# schematic.net
KiCad netlist of a schematic drawn in Altium Designer
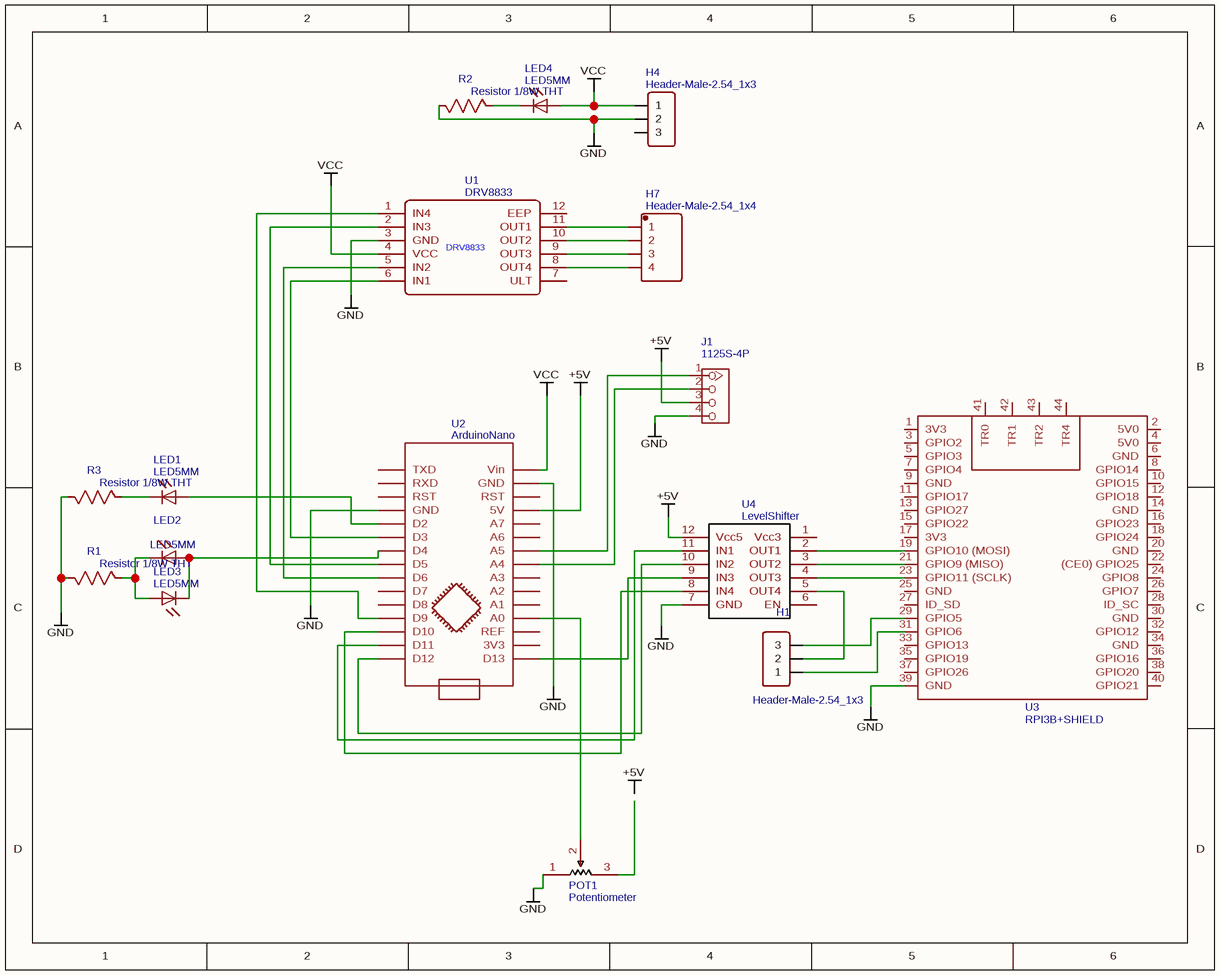
[diagram p0: schematic.schdoc]

(export (version "E")
  (design (tool "Eeschema 10.0.6"))
  (components
    (comp (ref "H1")
      (value "Header-Male-2.54_1x3")
      (fields
        (field (name "BOM_MANUFACTURER PART") "Header2.54mm 1*3P")
        (field (name "BOM_SUPPLIER PART") "C49257")
      )
      (libsource (lib "altium-import") (part "root_2_Header-Male-2.54_1x3_"))
    )
    (comp (ref "H4")
      (value "Header-Male-2.54_1x3")
      (fields
        (field (name "BOM_MANUFACTURER PART") "Header2.54mm 1*3P")
        (field (name "BOM_SUPPLIER PART") "C49257")
      )
      (libsource (lib "altium-import") (part "root_0_Header-Male-2.54_1x3_"))
    )
    (comp (ref "H7")
      (value "Header-Male-2.54_1x4")
      (fields
        (field (name "BOM_MANUFACTURER PART") "210S-1*4P L=11.6MMGold-plated black")
        (field (name "BOM_SUPPLIER PART") "C124378")
        (field (name "CONTRIBUTOR") "LCSC")
      )
      (libsource (lib "altium-import") (part "root_0_Header-Male-2.54_1x4_"))
    )
    (comp (ref "J1")
      (value "1125S-4P")
      (description "DIP Grove")
      (libsource (lib "altium-import") (part "root_0_1125S-4P_"))
    )
    (comp (ref "LED1")
      (value "LED5MM")
      (description "LEDs")
      (fields (field (name "CONTRIBUTOR") "Pinoccio"))
      (libsource (lib "altium-import") (part "root_3_LED5MM_"))
    )
    (comp (ref "LED2")
      (value "LED5MM")
      (description "LEDs")
      (fields (field (name "CONTRIBUTOR") "Pinoccio"))
      (libsource (lib "altium-import") (part "root_3_LED5MM_"))
    )
    (comp (ref "LED3")
      (value "LED5MM")
      (description "LEDs")
      (fields (field (name "CONTRIBUTOR") "Pinoccio"))
      (libsource (lib "altium-import") (part "root_1_LED5MM_"))
    )
    (comp (ref "LED4")
      (value "LED5MM")
      (description "LEDs")
      (fields (field (name "CONTRIBUTOR") "Pinoccio"))
      (libsource (lib "altium-import") (part "root_3_LED5MM_"))
    )
    (comp (ref "POT1")
      (value "Potentiometer")
      (fields
        (field (name "BOM_MANUFACTURER PART") "potentiometer")
        (field (name "CONTRIBUTOR") "Tommaso Mariotti")
      )
      (libsource (lib "altium-import") (part "root_0_Potentiometer_"))
    )
    (comp (ref "R1")
      (value "Resistor 1/8W THT")
      (fields (field (name "BOM_MANUFACTURER PART") "Generic") (field (name "CONTRIBUTOR") "tyvogelpohl"))
      (libsource (lib "altium-import") (part "root_2_Resistor 1/8W THT_"))
    )
    (comp (ref "R2")
      (value "Resistor 1/8W THT")
      (fields (field (name "BOM_MANUFACTURER PART") "Generic") (field (name "CONTRIBUTOR") "tyvogelpohl"))
      (libsource (lib "altium-import") (part "root_2_Resistor 1/8W THT_"))
    )
    (comp (ref "R3")
      (value "Resistor 1/8W THT")
      (fields (field (name "BOM_MANUFACTURER PART") "Generic") (field (name "CONTRIBUTOR") "tyvogelpohl"))
      (libsource (lib "altium-import") (part "root_2_Resistor 1/8W THT_"))
    )
    (comp (ref "U1") (value "DRV8833") (libsource (lib "altium-import") (part "root_0_DRV8833_")))
    (comp (ref "U2")
      (value "ArduinoNano")
      (fields (field (name "CONTRIBUTOR") "vincint810923"))
      (libsource (lib "altium-import") (part "root_0_ArduinoNano_"))
    )
    (comp (ref "U3")
      (value "RPI3B+SHIELD")
      (fields (field (name "BOM_MANUFACTURER PART") "RaspberryPi 3") (field (name "CONTRIBUTOR") "gdevries"))
      (libsource (lib "altium-import") (part "root_0_RPI3B+SHIELD_"))
    )
    (comp (ref "U4")
      (value "LevelShifter")
      (fields (field (name "CONTRIBUTOR") "max.helmrich"))
      (libsource (lib "altium-import") (part "root_0_LevelShifter_"))
    )
  )
  (nets
    (net (code "1") (name "+5V") (class "Default")
      (node (ref "J1") (pin "3") (pinfunction "3_3") (pintype "passive"))
      (node (ref "U2") (pin "27") (pinfunction "5V_27") (pintype "passive"))
      (node (ref "U4") (pin "12") (pinfunction "Vcc5_12") (pintype "passive"))
    )
    (net (code "2") (name "GND") (class "Default")
      (node (ref "H4") (pin "2") (pinfunction "2_2") (pintype "passive"))
      (node (ref "J1") (pin "4") (pinfunction "4_4") (pintype "passive"))
      (node (ref "POT1") (pin "1") (pinfunction "1_1") (pintype "passive"))
      (node (ref "R1") (pin "2") (pinfunction "2_2") (pintype "passive"))
      (node (ref "R2") (pin "2") (pinfunction "2_2") (pintype "passive"))
      (node (ref "R3") (pin "2") (pinfunction "2_2") (pintype "passive"))
      (node (ref "U1") (pin "3") (pinfunction "GND_3") (pintype "passive"))
      (node (ref "U2") (pin "29") (pinfunction "GND_29") (pintype "passive"))
      (node (ref "U2") (pin "4") (pinfunction "GND_4") (pintype "passive"))
      (node (ref "U3") (pin "39") (pinfunction "GND_39") (pintype "passive"))
      (node (ref "U4") (pin "7") (pinfunction "GND_7") (pintype "passive"))
    )
    (net (code "3") (name "Net-(LED1-C)") (class "Default")
      (node (ref "LED1") (pin "K") (pinfunction "C_K") (pintype "passive"))
      (node (ref "R3") (pin "1") (pinfunction "1_1") (pintype "passive"))
    )
    (net (code "4") (name "Net-(LED2-C)") (class "Default")
      (node (ref "LED2") (pin "K") (pinfunction "C_K") (pintype "passive"))
      (node (ref "LED3") (pin "A") (pinfunction "A_A") (pintype "passive"))
      (node (ref "R1") (pin "1") (pinfunction "1_1") (pintype "passive"))
    )
    (net (code "5") (name "Net-(LED3-C)") (class "Default")
      (node (ref "LED2") (pin "A") (pinfunction "A_A") (pintype "passive"))
      (node (ref "LED3") (pin "K") (pinfunction "C_K") (pintype "passive"))
      (node (ref "U2") (pin "7") (pinfunction "D4_7") (pintype "passive"))
    )
    (net (code "6") (name "Net-(LED4-C)") (class "Default")
      (node (ref "LED4") (pin "K") (pinfunction "C_K") (pintype "passive"))
      (node (ref "R2") (pin "1") (pinfunction "1_1") (pintype "passive"))
    )
    (net (code "7") (name "Net-(U1-IN1)") (class "Default")
      (node (ref "U1") (pin "6") (pinfunction "IN1_6") (pintype "passive"))
      (node (ref "U2") (pin "6") (pinfunction "D3_6") (pintype "passive"))
    )
    (net (code "8") (name "Net-(U1-IN2)") (class "Default")
      (node (ref "U1") (pin "5") (pinfunction "IN2_5") (pintype "passive"))
      (node (ref "U2") (pin "9") (pinfunction "D6_9") (pintype "passive"))
    )
    (net (code "9") (name "Net-(U1-IN3)") (class "Default")
      (node (ref "U1") (pin "2") (pinfunction "IN3_2") (pintype "passive"))
      (node (ref "U2") (pin "8") (pinfunction "D5_8") (pintype "passive"))
    )
    (net (code "10") (name "Net-(U1-IN4)") (class "Default")
      (node (ref "U1") (pin "1") (pinfunction "IN4_1") (pintype "passive"))
      (node (ref "U2") (pin "12") (pinfunction "D9_12") (pintype "passive"))
    )
    (net (code "11") (name "Net-(U1-OUT1)") (class "Default")
      (node (ref "H7") (pin "1") (pinfunction "1_1") (pintype "passive"))
      (node (ref "U1") (pin "11") (pinfunction "OUT1_11") (pintype "passive"))
    )
    (net (code "12") (name "Net-(U1-OUT2)") (class "Default")
      (node (ref "H7") (pin "2") (pinfunction "2_2") (pintype "passive"))
      (node (ref "U1") (pin "10") (pinfunction "OUT2_10") (pintype "passive"))
    )
    (net (code "13") (name "Net-(U1-OUT3)") (class "Default")
      (node (ref "H7") (pin "3") (pinfunction "3_3") (pintype "passive"))
      (node (ref "U1") (pin "9") (pinfunction "OUT3_9") (pintype "passive"))
    )
    (net (code "14") (name "Net-(U1-OUT4)") (class "Default")
      (node (ref "H7") (pin "4") (pinfunction "4_4") (pintype "passive"))
      (node (ref "U1") (pin "8") (pinfunction "OUT4_8") (pintype "passive"))
    )
    (net (code "15") (name "Net-(U2-A0)") (class "Default")
      (node (ref "POT1") (pin "2") (pinfunction "2_2") (pintype "passive"))
      (node (ref "U2") (pin "19") (pinfunction "A0_19") (pintype "passive"))
    )
    (net (code "16") (name "Net-(U2-A4)") (class "Default")
      (node (ref "J1") (pin "2") (pinfunction "2_2") (pintype "passive"))
      (node (ref "U2") (pin "23") (pinfunction "A4_23") (pintype "passive"))
    )
    (net (code "17") (name "Net-(U2-A5)") (class "Default")
      (node (ref "J1") (pin "1") (pinfunction "1_1") (pintype "passive"))
      (node (ref "U2") (pin "24") (pinfunction "A5_24") (pintype "passive"))
    )
    (net (code "18") (name "Net-(U2-D2)") (class "Default")
      (node (ref "LED1") (pin "A") (pinfunction "A_A") (pintype "passive"))
      (node (ref "U2") (pin "5") (pinfunction "D2_5") (pintype "passive"))
    )
    (net (code "19") (name "Net-(U2-D10)") (class "Default")
      (node (ref "U2") (pin "13") (pinfunction "D10_13") (pintype "passive"))
      (node (ref "U4") (pin "8") (pinfunction "IN4_8") (pintype "passive"))
    )
    (net (code "20") (name "Net-(U2-D11)") (class "Default")
      (node (ref "U2") (pin "14") (pinfunction "D11_14") (pintype "passive"))
      (node (ref "U4") (pin "11") (pinfunction "IN1_11") (pintype "passive"))
    )
    (net (code "21") (name "Net-(U2-D12)") (class "Default")
      (node (ref "U2") (pin "15") (pinfunction "D12_15") (pintype "passive"))
      (node (ref "U4") (pin "10") (pinfunction "IN2_10") (pintype "passive"))
    )
    (net (code "22") (name "Net-(U2-D13)") (class "Default")
      (node (ref "U2") (pin "16") (pinfunction "D13_16") (pintype "passive"))
      (node (ref "U4") (pin "9") (pinfunction "IN3_9") (pintype "passive"))
    )
    (net (code "23") (name "Net-(U3-GPIO5)") (class "Default")
      (node (ref "H1") (pin "3") (pinfunction "3_3") (pintype "passive"))
      (node (ref "U3") (pin "29") (pinfunction "GPIO5_29") (pintype "passive"))
    )
    (net (code "24") (name "Net-(U3-GPIO6)") (class "Default")
      (node (ref "H1") (pin "1") (pinfunction "1_1") (pintype "passive"))
      (node (ref "U3") (pin "31") (pinfunction "GPIO6_31") (pintype "passive"))
    )
    (net (code "25") (name "Net-(U3-GPIO9_(MISO))") (class "Default")
      (node (ref "U3") (pin "21") (pinfunction "GPIO9_(MISO)_21") (pintype "passive"))
      (node (ref "U4") (pin "3") (pinfunction "OUT2_3") (pintype "passive"))
    )
    (net (code "26") (name "Net-(U3-GPIO10_(MOSI))") (class "Default")
      (node (ref "U3") (pin "19") (pinfunction "GPIO10_(MOSI)_19") (pintype "passive"))
      (node (ref "U4") (pin "2") (pinfunction "OUT1_2") (pintype "passive"))
    )
    (net (code "27") (name "Net-(U3-GPIO11_(SCLK))") (class "Default")
      (node (ref "U3") (pin "23") (pinfunction "GPIO11_(SCLK)_23") (pintype "passive"))
      (node (ref "U4") (pin "4") (pinfunction "OUT3_4") (pintype "passive"))
    )
    (net (code "28") (name "Net-(U4-OUT4)") (class "Default")
      (node (ref "H1") (pin "2") (pinfunction "2_2") (pintype "passive"))
      (node (ref "U4") (pin "5") (pinfunction "OUT4_5") (pintype "passive"))
    )
    (net (code "29") (name "VCC") (class "Default")
      (node (ref "H4") (pin "1") (pinfunction "1_1") (pintype "passive"))
      (node (ref "LED4") (pin "A") (pinfunction "A_A") (pintype "passive"))
      (node (ref "U1") (pin "4") (pinfunction "VCC_4") (pintype "passive"))
      (node (ref "U2") (pin "30") (pinfunction "Vin_30") (pintype "passive"))
    )
    (net (code "30") (name "unconnected-(H4-Pad3)") (class "Default")
      (node (ref "H4") (pin "3") (pinfunction "3_3") (pintype "passive"))
    )
    (net (code "31") (name "unconnected-(POT1-Pad3)") (class "Default")
      (node (ref "POT1") (pin "3") (pinfunction "3_3") (pintype "passive"))
    )
    (net (code "32") (name "unconnected-(U1-EEP-Pad12)") (class "Default")
      (node (ref "U1") (pin "12") (pinfunction "EEP_12") (pintype "passive"))
    )
    (net (code "33") (name "unconnected-(U1-ULT-Pad7)") (class "Default")
      (node (ref "U1") (pin "7") (pinfunction "ULT_7") (pintype "passive"))
    )
    (net (code "34") (name "unconnected-(U2-3V3-Pad17)") (class "Default")
      (node (ref "U2") (pin "17") (pinfunction "3V3_17") (pintype "passive"))
    )
    (net (code "35") (name "unconnected-(U2-A1-Pad20)") (class "Default")
      (node (ref "U2") (pin "20") (pinfunction "A1_20") (pintype "passive"))
    )
    (net (code "36") (name "unconnected-(U2-A2-Pad21)") (class "Default")
      (node (ref "U2") (pin "21") (pinfunction "A2_21") (pintype "passive"))
    )
    (net (code "37") (name "unconnected-(U2-A3-Pad22)") (class "Default")
      (node (ref "U2") (pin "22") (pinfunction "A3_22") (pintype "passive"))
    )
    (net (code "38") (name "unconnected-(U2-A6-Pad25)") (class "Default")
      (node (ref "U2") (pin "25") (pinfunction "A6_25") (pintype "passive"))
    )
    (net (code "39") (name "unconnected-(U2-A7-Pad26)") (class "Default")
      (node (ref "U2") (pin "26") (pinfunction "A7_26") (pintype "passive"))
    )
    (net (code "40") (name "unconnected-(U2-D7-Pad10)") (class "Default")
      (node (ref "U2") (pin "10") (pinfunction "D7_10") (pintype "passive"))
    )
    (net (code "41") (name "unconnected-(U2-D8-Pad11)") (class "Default")
      (node (ref "U2") (pin "11") (pinfunction "D8_11") (pintype "passive"))
    )
    (net (code "42") (name "unconnected-(U2-REF-Pad18)") (class "Default")
      (node (ref "U2") (pin "18") (pinfunction "REF_18") (pintype "passive"))
    )
    (net (code "43") (name "unconnected-(U2-RST-Pad3)") (class "Default")
      (node (ref "U2") (pin "3") (pinfunction "RST_3") (pintype "passive"))
    )
    (net (code "44") (name "unconnected-(U2-RST-Pad28)") (class "Default")
      (node (ref "U2") (pin "28") (pinfunction "RST_28") (pintype "passive"))
    )
    (net (code "45") (name "unconnected-(U2-RXD-Pad2)") (class "Default")
      (node (ref "U2") (pin "2") (pinfunction "RXD_2") (pintype "passive"))
    )
    (net (code "46") (name "unconnected-(U2-TXD-Pad1)") (class "Default")
      (node (ref "U2") (pin "1") (pinfunction "TXD_1") (pintype "passive"))
    )
    (net (code "47") (name "unconnected-(U3-(CE0)_GPIO25-Pad22)") (class "Default")
      (node (ref "U3") (pin "22") (pinfunction "(CE0)_GPIO25_22") (pintype "passive"))
    )
    (net (code "48") (name "unconnected-(U3-3V3-Pad1)") (class "Default")
      (node (ref "U3") (pin "1") (pinfunction "3V3_1") (pintype "passive"))
    )
    (net (code "49") (name "unconnected-(U3-3V3-Pad17)") (class "Default")
      (node (ref "U3") (pin "17") (pinfunction "3V3_17") (pintype "passive"))
    )
    (net (code "50") (name "unconnected-(U3-5V0-Pad2)") (class "Default")
      (node (ref "U3") (pin "2") (pinfunction "5V0_2") (pintype "passive"))
    )
    (net (code "51") (name "unconnected-(U3-5V0-Pad4)") (class "Default")
      (node (ref "U3") (pin "4") (pinfunction "5V0_4") (pintype "passive"))
    )
    (net (code "52") (name "unconnected-(U3-GND-Pad6)") (class "Default")
      (node (ref "U3") (pin "6") (pinfunction "GND_6") (pintype "passive"))
    )
    (net (code "53") (name "unconnected-(U3-GND-Pad9)") (class "Default")
      (node (ref "U3") (pin "9") (pinfunction "GND_9") (pintype "passive"))
    )
    (net (code "54") (name "unconnected-(U3-GND-Pad14)") (class "Default")
      (node (ref "U3") (pin "14") (pinfunction "GND_14") (pintype "passive"))
    )
    (net (code "55") (name "unconnected-(U3-GND-Pad20)") (class "Default")
      (node (ref "U3") (pin "20") (pinfunction "GND_20") (pintype "passive"))
    )
    (net (code "56") (name "unconnected-(U3-GND-Pad25)") (class "Default")
      (node (ref "U3") (pin "25") (pinfunction "GND_25") (pintype "passive"))
    )
    (net (code "57") (name "unconnected-(U3-GND-Pad30)") (class "Default")
      (node (ref "U3") (pin "30") (pinfunction "GND_30") (pintype "passive"))
    )
    (net (code "58") (name "unconnected-(U3-GND-Pad34)") (class "Default")
      (node (ref "U3") (pin "34") (pinfunction "GND_34") (pintype "passive"))
    )
    (net (code "59") (name "unconnected-(U3-GPIO2-Pad3)") (class "Default")
      (node (ref "U3") (pin "3") (pinfunction "GPIO2_3") (pintype "passive"))
    )
    (net (code "60") (name "unconnected-(U3-GPIO3-Pad5)") (class "Default")
      (node (ref "U3") (pin "5") (pinfunction "GPIO3_5") (pintype "passive"))
    )
    (net (code "61") (name "unconnected-(U3-GPIO4-Pad7)") (class "Default")
      (node (ref "U3") (pin "7") (pinfunction "GPIO4_7") (pintype "passive"))
    )
    (net (code "62") (name "unconnected-(U3-GPIO7-Pad26)") (class "Default")
      (node (ref "U3") (pin "26") (pinfunction "GPIO7_26") (pintype "passive"))
    )
    (net (code "63") (name "unconnected-(U3-GPIO8-Pad24)") (class "Default")
      (node (ref "U3") (pin "24") (pinfunction "GPIO8_24") (pintype "passive"))
    )
    (net (code "64") (name "unconnected-(U3-GPIO12-Pad32)") (class "Default")
      (node (ref "U3") (pin "32") (pinfunction "GPIO12_32") (pintype "passive"))
    )
    (net (code "65") (name "unconnected-(U3-GPIO13-Pad33)") (class "Default")
      (node (ref "U3") (pin "33") (pinfunction "GPIO13_33") (pintype "passive"))
    )
    (net (code "66") (name "unconnected-(U3-GPIO14-Pad8)") (class "Default")
      (node (ref "U3") (pin "8") (pinfunction "GPIO14_8") (pintype "passive"))
    )
    (net (code "67") (name "unconnected-(U3-GPIO15-Pad10)") (class "Default")
      (node (ref "U3") (pin "10") (pinfunction "GPIO15_10") (pintype "passive"))
    )
    (net (code "68") (name "unconnected-(U3-GPIO16-Pad36)") (class "Default")
      (node (ref "U3") (pin "36") (pinfunction "GPIO16_36") (pintype "passive"))
    )
    (net (code "69") (name "unconnected-(U3-GPIO17-Pad11)") (class "Default")
      (node (ref "U3") (pin "11") (pinfunction "GPIO17_11") (pintype "passive"))
    )
    (net (code "70") (name "unconnected-(U3-GPIO18-Pad12)") (class "Default")
      (node (ref "U3") (pin "12") (pinfunction "GPIO18_12") (pintype "passive"))
    )
    (net (code "71") (name "unconnected-(U3-GPIO19-Pad35)") (class "Default")
      (node (ref "U3") (pin "35") (pinfunction "GPIO19_35") (pintype "passive"))
    )
    (net (code "72") (name "unconnected-(U3-GPIO20-Pad38)") (class "Default")
      (node (ref "U3") (pin "38") (pinfunction "GPIO20_38") (pintype "passive"))
    )
    (net (code "73") (name "unconnected-(U3-GPIO21-Pad40)") (class "Default")
      (node (ref "U3") (pin "40") (pinfunction "GPIO21_40") (pintype "passive"))
    )
    (net (code "74") (name "unconnected-(U3-GPIO22-Pad15)") (class "Default")
      (node (ref "U3") (pin "15") (pinfunction "GPIO22_15") (pintype "passive"))
    )
    (net (code "75") (name "unconnected-(U3-GPIO23-Pad16)") (class "Default")
      (node (ref "U3") (pin "16") (pinfunction "GPIO23_16") (pintype "passive"))
    )
    (net (code "76") (name "unconnected-(U3-GPIO24-Pad18)") (class "Default")
      (node (ref "U3") (pin "18") (pinfunction "GPIO24_18") (pintype "passive"))
    )
    (net (code "77") (name "unconnected-(U3-GPIO26-Pad37)") (class "Default")
      (node (ref "U3") (pin "37") (pinfunction "GPIO26_37") (pintype "passive"))
    )
    (net (code "78") (name "unconnected-(U3-GPIO27-Pad13)") (class "Default")
      (node (ref "U3") (pin "13") (pinfunction "GPIO27_13") (pintype "passive"))
    )
    (net (code "79") (name "unconnected-(U3-ID_SC-Pad28)") (class "Default")
      (node (ref "U3") (pin "28") (pinfunction "ID_SC_28") (pintype "passive"))
    )
    (net (code "80") (name "unconnected-(U3-ID_SD-Pad27)") (class "Default")
      (node (ref "U3") (pin "27") (pinfunction "ID_SD_27") (pintype "passive"))
    )
    (net (code "81") (name "unconnected-(U3-TR0-Pad41)") (class "Default")
      (node (ref "U3") (pin "41") (pinfunction "TR0_41") (pintype "passive"))
    )
    (net (code "82") (name "unconnected-(U3-TR1-Pad42)") (class "Default")
      (node (ref "U3") (pin "42") (pinfunction "TR1_42") (pintype "passive"))
    )
    (net (code "83") (name "unconnected-(U3-TR2-Pad43)") (class "Default")
      (node (ref "U3") (pin "43") (pinfunction "TR2_43") (pintype "passive"))
    )
    (net (code "84") (name "unconnected-(U3-TR4-Pad44)") (class "Default")
      (node (ref "U3") (pin "44") (pinfunction "TR4_44") (pintype "passive"))
    )
    (net (code "85") (name "unconnected-(U4-EN-Pad6)") (class "Default")
      (node (ref "U4") (pin "6") (pinfunction "EN_6") (pintype "passive"))
    )
    (net (code "86") (name "unconnected-(U4-Vcc3-Pad1)") (class "Default")
      (node (ref "U4") (pin "1") (pinfunction "Vcc3_1") (pintype "passive"))
    )
  )
)
